# 150308-1-eRIC-Nitro-v1_2.net
KiCad netlist of a schematic drawn in EAGLE
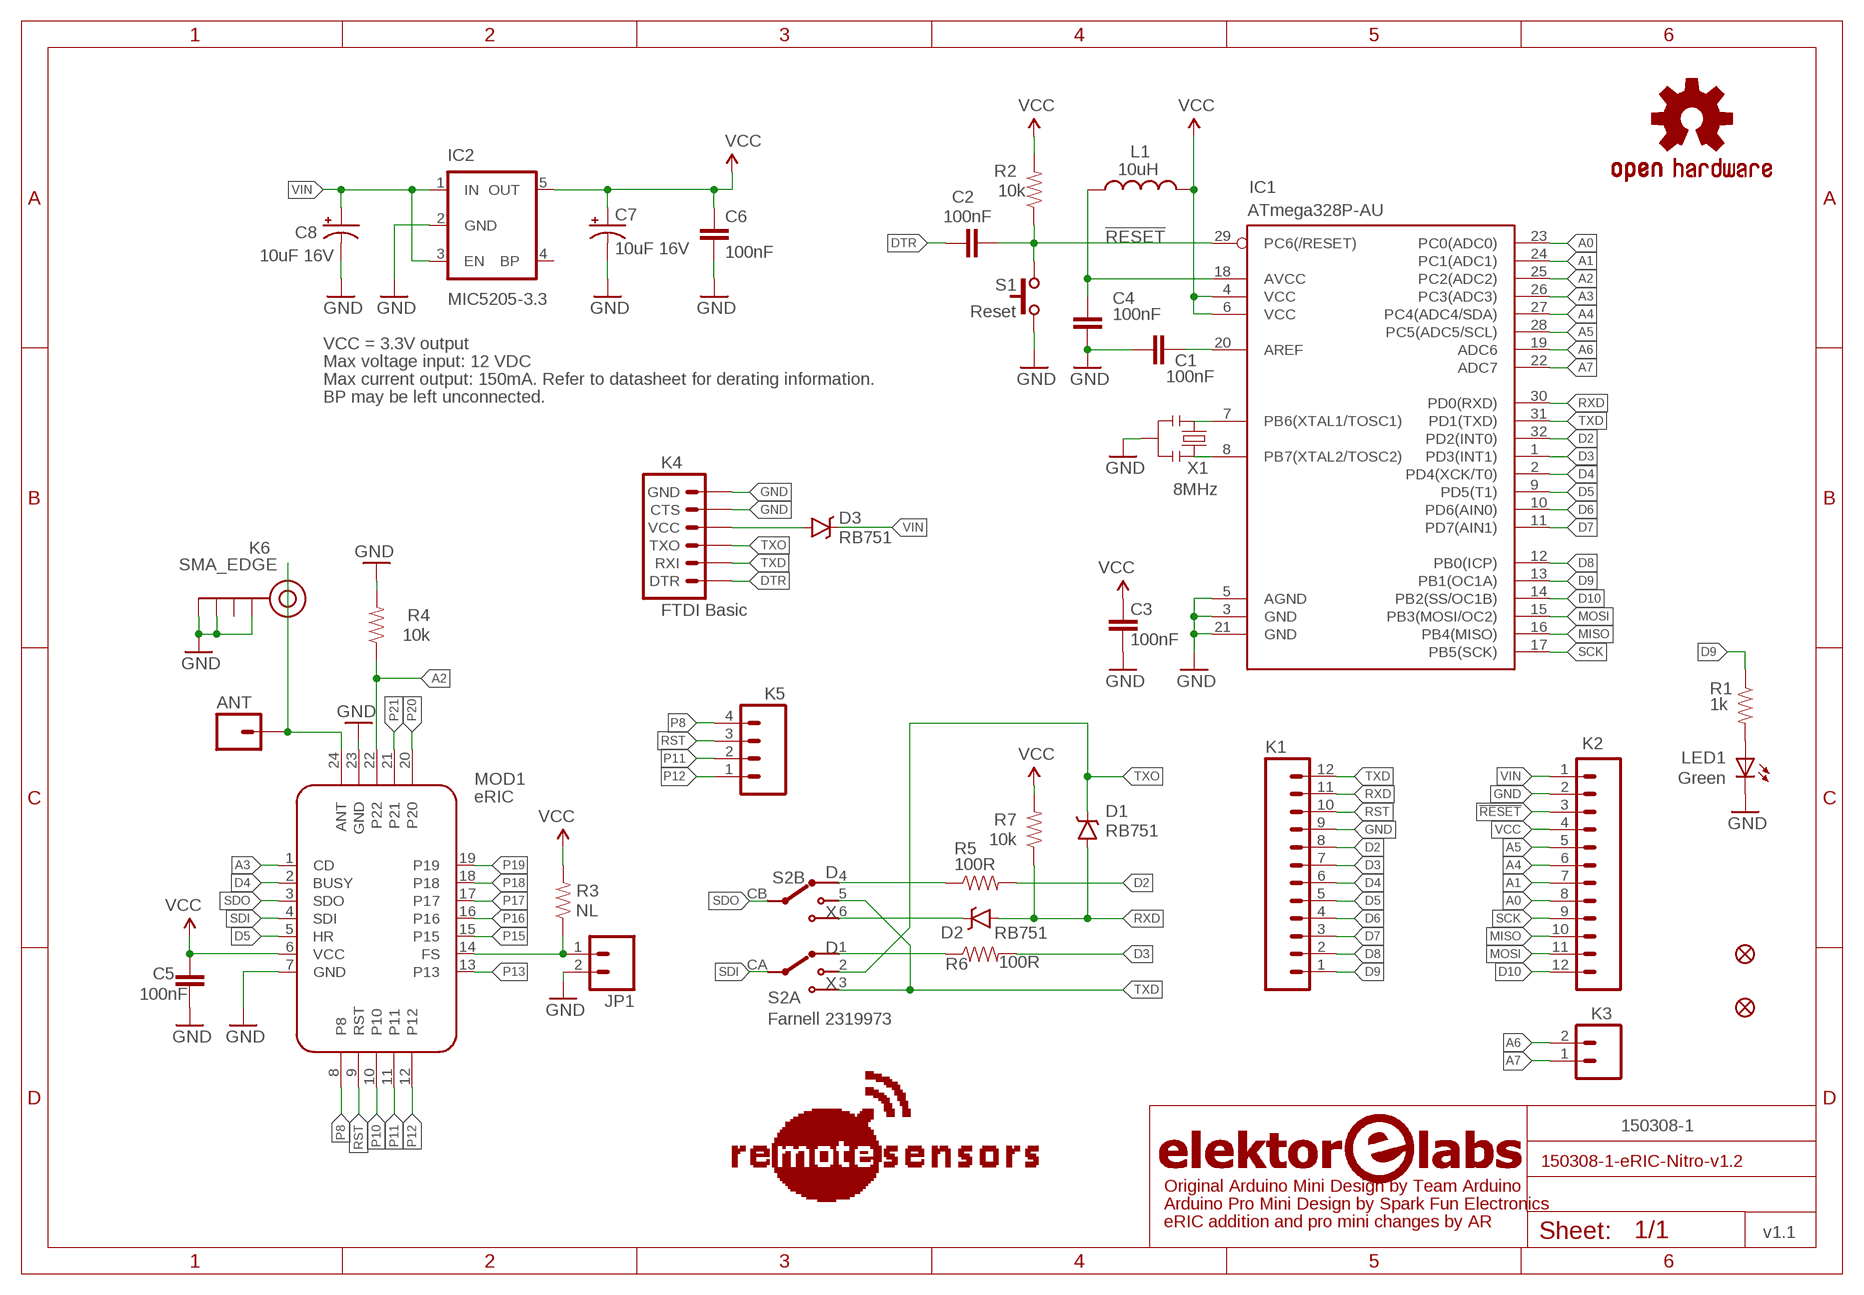
[diagram p0: schematic, sheet 1]

(export (version "E")
  (design (tool "Eeschema 10.0.6"))
  (components
    (comp (ref "ANT")
      (value "M01PTH")
      (footprint "eagle-import:1X01-080")
      (libsource (lib "eagle-import") (part "M01PTH"))
    )
    (comp (ref "C1")
      (value "100nF")
      (footprint "eagle-import:0603-CAP")
      (libsource (lib "eagle-import") (part "CAP0603-CAP"))
    )
    (comp (ref "C2")
      (value "100nF")
      (footprint "eagle-import:0603-CAP")
      (libsource (lib "eagle-import") (part "CAP0603-CAP"))
    )
    (comp (ref "C3")
      (value "100nF")
      (footprint "eagle-import:0603-CAP")
      (libsource (lib "eagle-import") (part "CAP0603-CAP"))
    )
    (comp (ref "C4")
      (value "100nF")
      (footprint "eagle-import:0603-CAP")
      (libsource (lib "eagle-import") (part "CAP0603-CAP"))
    )
    (comp (ref "C5")
      (value "100nF")
      (footprint "eagle-import:0603-CAP")
      (libsource (lib "eagle-import") (part "CAP0603-CAP"))
    )
    (comp (ref "C6")
      (value "100nF")
      (footprint "eagle-import:0603-CAP")
      (libsource (lib "eagle-import") (part "CAP0603-CAP"))
    )
    (comp (ref "C7")
      (value "10uF 16V")
      (footprint "eagle-import:EIA3216")
      (libsource (lib "eagle-import") (part "CAP_POL1206"))
    )
    (comp (ref "C8")
      (value "10uF 16V")
      (footprint "eagle-import:EIA3216")
      (libsource (lib "eagle-import") (part "CAP_POL1206"))
    )
    (comp (ref "D1")
      (value "RB751")
      (footprint "eagle-import:SOD-523")
      (libsource (lib "eagle-import") (part "RB751"))
    )
    (comp (ref "D2")
      (value "RB751")
      (footprint "eagle-import:SOD-523")
      (libsource (lib "eagle-import") (part "RB751"))
    )
    (comp (ref "D3")
      (value "RB751")
      (footprint "eagle-import:SOD-523")
      (libsource (lib "eagle-import") (part "RB751"))
    )
    (comp (ref "FID1")
      (value "FIDUCIALUFIDUCIAL")
      (footprint "eagle-import:MICRO-FIDUCIAL")
      (libsource (lib "eagle-import") (part "FIDUCIALUFIDUCIAL"))
    )
    (comp (ref "FID2")
      (value "FIDUCIALUFIDUCIAL")
      (footprint "eagle-import:MICRO-FIDUCIAL")
      (libsource (lib "eagle-import") (part "FIDUCIALUFIDUCIAL"))
    )
    (comp (ref "IC1")
      (value "ATmega328P-AU")
      (footprint "eagle-import:TQFP32-08")
      (libsource (lib "eagle-import") (part "ATMEGA168"))
    )
    (comp (ref "IC2")
      (value "MIC5205-3.3")
      (footprint "eagle-import:SOT23-5")
      (libsource (lib "eagle-import") (part "V_REG_LDOSMD"))
    )
    (comp (ref "JP1")
      (value "M02PTH")
      (footprint "eagle-import:1X02")
      (libsource (lib "eagle-import") (part "M02PTH"))
    )
    (comp (ref "K1")
      (value "M12PTH")
      (footprint "eagle-import:1X12")
      (libsource (lib "eagle-import") (part "M12PTH"))
    )
    (comp (ref "K2")
      (value "M12PTH")
      (footprint "eagle-import:1X12")
      (libsource (lib "eagle-import") (part "M12PTH"))
    )
    (comp (ref "K3")
      (value "M02PTH")
      (footprint "eagle-import:1X02")
      (libsource (lib "eagle-import") (part "M02PTH"))
    )
    (comp (ref "K4")
      (value "FTDI Basic")
      (footprint "eagle-import:1X06")
      (libsource (lib "eagle-import") (part "ARDUINO_SERIAL_PROGRAMPTH"))
    )
    (comp (ref "K5")
      (value "M04PTH")
      (footprint "eagle-import:1X04")
      (libsource (lib "eagle-import") (part "M04PTH"))
    )
    (comp (ref "K6")
      (value "SMA_EDGE")
      (footprint "eagle-import:SMA-EDGE")
      (libsource (lib "eagle-import") (part "SMA_EDGE"))
    )
    (comp (ref "L1")
      (value "10uH")
      (footprint "eagle-import:0603")
      (libsource (lib "eagle-import") (part "INDUCTOR0603"))
    )
    (comp (ref "LED1")
      (value "Green")
      (footprint "eagle-import:0603-LED-ALT1")
      (libsource (lib "eagle-import") (part "LED"))
    )
    (comp (ref "LOGO1")
      (value "OSHW-LOGOS")
      (footprint "eagle-import:OSHW-LOGO-S")
      (libsource (lib "eagle-import") (part "OSHW-LOGOS"))
    )
    (comp (ref "LOGO2")
      (value "LOGO-ELEKTOR-LABS-25MM")
      (footprint "eagle-import:ELPP-LOGO-ELEKTOR-LABS-25MM")
      (libsource (lib "eagle-import") (part "LOGO-ELEKTOR-LABS-25MM"))
    )
    (comp (ref "LOGO3")
      (value "LOGO-REMOTE-SENSORS-17MM")
      (footprint "eagle-import:LOGO-REMOTE-SENSORS2")
      (libsource (lib "eagle-import") (part "LOGO-REMOTE-SENSORS-17MM"))
    )
    (comp (ref "MOD1")
      (value "eRIC")
      (footprint "eagle-import:ERIC")
      (libsource (lib "eagle-import") (part "ERIC"))
    )
    (comp (ref "R1")
      (value "1k")
      (footprint "eagle-import:0603-RES")
      (libsource (lib "eagle-import") (part "RESISTOR0603-RES"))
    )
    (comp (ref "R2")
      (value "10k")
      (footprint "eagle-import:0603-RES")
      (libsource (lib "eagle-import") (part "RESISTOR0603-RES"))
    )
    (comp (ref "R3")
      (value "NL")
      (footprint "eagle-import:0603-RES")
      (libsource (lib "eagle-import") (part "RESISTOR0603-RES"))
    )
    (comp (ref "R4")
      (value "10k")
      (footprint "eagle-import:0603-RES")
      (libsource (lib "eagle-import") (part "RESISTOR0603-RES"))
    )
    (comp (ref "R5")
      (value "100R")
      (footprint "eagle-import:0603-RES")
      (libsource (lib "eagle-import") (part "SparkFun-Resistors_RESISTOR0603-RES"))
    )
    (comp (ref "R6")
      (value "100R")
      (footprint "eagle-import:0603-RES")
      (libsource (lib "eagle-import") (part "SparkFun-Resistors_RESISTOR0603-RES"))
    )
    (comp (ref "R7")
      (value "10k")
      (footprint "eagle-import:0603-RES")
      (libsource (lib "eagle-import") (part "RESISTOR0603-RES"))
    )
    (comp (ref "S1")
      (value "Reset")
      (footprint "eagle-import:TACTILE-SWITCH-SMD-ALT04")
      (libsource (lib "eagle-import") (part "SWITCH-MOMENTARY-2SMD-ALT04"))
    )
    (comp (ref "S2")
      (value "AYZ0203AGRLC")
      (footprint "eagle-import:AYZ0203")
      (libsource (lib "eagle-import") (part "AYZ0203AGRLC"))
    )
    (comp (ref "X1")
      (value "8MHz")
      (footprint "eagle-import:RESONATOR-SMD")
      (libsource (lib "eagle-import") (part "RESONATORSMD"))
    )
  )
  (nets
    (net (code "1") (name "/~{RESET}") (class "Default")
      (node (ref "C2") (pin "1") (pinfunction "1_1") (pintype "passive"))
      (node (ref "IC1") (pin "29") (pinfunction "PC6(/RESET)_29") (pintype "bidirectional"))
      (node (ref "K2") (pin "3") (pinfunction "3_3") (pintype "passive"))
      (node (ref "R2") (pin "1") (pinfunction "1_1") (pintype "passive"))
      (node (ref "S1") (pin "3") (pinfunction "2_3") (pintype "passive"))
      (node (ref "S1") (pin "4") (pinfunction "2_4") (pintype "passive"))
    )
    (net (code "2") (name "A0") (class "Default")
      (node (ref "IC1") (pin "23") (pinfunction "PC0(ADC0)_23") (pintype "bidirectional"))
      (node (ref "K2") (pin "8") (pinfunction "8_8") (pintype "passive"))
    )
    (net (code "3") (name "A1") (class "Default")
      (node (ref "IC1") (pin "24") (pinfunction "PC1(ADC1)_24") (pintype "bidirectional"))
      (node (ref "K2") (pin "7") (pinfunction "7_7") (pintype "passive"))
    )
    (net (code "4") (name "A2") (class "Default")
      (node (ref "IC1") (pin "25") (pinfunction "PC2(ADC2)_25") (pintype "bidirectional"))
      (node (ref "MOD1") (pin "22") (pinfunction "P22_22") (pintype "bidirectional"))
      (node (ref "R4") (pin "1") (pinfunction "1_1") (pintype "passive"))
    )
    (net (code "5") (name "A3") (class "Default")
      (node (ref "IC1") (pin "26") (pinfunction "PC3(ADC3)_26") (pintype "bidirectional"))
      (node (ref "MOD1") (pin "1") (pinfunction "CD_1") (pintype "bidirectional"))
    )
    (net (code "6") (name "A4") (class "Default")
      (node (ref "IC1") (pin "27") (pinfunction "PC4(ADC4/SDA)_27") (pintype "bidirectional"))
      (node (ref "K2") (pin "6") (pinfunction "6_6") (pintype "passive"))
    )
    (net (code "7") (name "A5") (class "Default")
      (node (ref "IC1") (pin "28") (pinfunction "PC5(ADC5/SCL)_28") (pintype "bidirectional"))
      (node (ref "K2") (pin "5") (pinfunction "5_5") (pintype "passive"))
    )
    (net (code "8") (name "A6") (class "Default")
      (node (ref "IC1") (pin "19") (pinfunction "ADC6_19") (pintype "bidirectional"))
      (node (ref "K3") (pin "2") (pinfunction "2_2") (pintype "passive"))
    )
    (net (code "9") (name "A7") (class "Default")
      (node (ref "IC1") (pin "22") (pinfunction "ADC7_22") (pintype "bidirectional"))
      (node (ref "K3") (pin "1") (pinfunction "1_1") (pintype "passive"))
    )
    (net (code "10") (name "D2") (class "Default")
      (node (ref "IC1") (pin "32") (pinfunction "PD2(INT0)_32") (pintype "bidirectional"))
      (node (ref "K1") (pin "8") (pinfunction "8_8") (pintype "passive"))
      (node (ref "R5") (pin "2") (pinfunction "2_2") (pintype "passive"))
    )
    (net (code "11") (name "D3") (class "Default")
      (node (ref "IC1") (pin "1") (pinfunction "PD3(INT1)_1") (pintype "bidirectional"))
      (node (ref "K1") (pin "7") (pinfunction "7_7") (pintype "passive"))
      (node (ref "R6") (pin "2") (pinfunction "2_2") (pintype "passive"))
    )
    (net (code "12") (name "D4") (class "Default")
      (node (ref "IC1") (pin "2") (pinfunction "PD4(XCK/T0)_2") (pintype "bidirectional"))
      (node (ref "K1") (pin "6") (pinfunction "6_6") (pintype "passive"))
      (node (ref "MOD1") (pin "2") (pinfunction "BUSY_2") (pintype "bidirectional"))
    )
    (net (code "13") (name "D5") (class "Default")
      (node (ref "IC1") (pin "9") (pinfunction "PD5(T1)_9") (pintype "bidirectional"))
      (node (ref "K1") (pin "5") (pinfunction "5_5") (pintype "passive"))
      (node (ref "MOD1") (pin "5") (pinfunction "HR_5") (pintype "bidirectional"))
    )
    (net (code "14") (name "D6") (class "Default")
      (node (ref "IC1") (pin "10") (pinfunction "PD6(AIN0)_10") (pintype "bidirectional"))
      (node (ref "K1") (pin "4") (pinfunction "4_4") (pintype "passive"))
    )
    (net (code "15") (name "D7") (class "Default")
      (node (ref "IC1") (pin "11") (pinfunction "PD7(AIN1)_11") (pintype "bidirectional"))
      (node (ref "K1") (pin "3") (pinfunction "3_3") (pintype "passive"))
    )
    (net (code "16") (name "D8") (class "Default")
      (node (ref "IC1") (pin "12") (pinfunction "PB0(ICP)_12") (pintype "bidirectional"))
      (node (ref "K1") (pin "2") (pinfunction "2_2") (pintype "passive"))
    )
    (net (code "17") (name "D9") (class "Default")
      (node (ref "IC1") (pin "13") (pinfunction "PB1(OC1A)_13") (pintype "bidirectional"))
      (node (ref "K1") (pin "1") (pinfunction "1_1") (pintype "passive"))
      (node (ref "R1") (pin "1") (pinfunction "1_1") (pintype "passive"))
    )
    (net (code "18") (name "D10") (class "Default")
      (node (ref "IC1") (pin "14") (pinfunction "PB2(SS/OC1B)_14") (pintype "bidirectional"))
      (node (ref "K2") (pin "12") (pinfunction "12_12") (pintype "passive"))
    )
    (net (code "19") (name "DTR") (class "Default")
      (node (ref "C2") (pin "2") (pinfunction "2_2") (pintype "passive"))
      (node (ref "K4") (pin "1") (pinfunction "DTR_1") (pintype "passive"))
    )
    (net (code "20") (name "GND") (class "Default")
      (node (ref "C1") (pin "1") (pinfunction "1_1") (pintype "passive"))
      (node (ref "C3") (pin "1") (pinfunction "1_1") (pintype "passive"))
      (node (ref "C4") (pin "1") (pinfunction "1_1") (pintype "passive"))
      (node (ref "C5") (pin "1") (pinfunction "1_1") (pintype "passive"))
      (node (ref "C6") (pin "2") (pinfunction "2_2") (pintype "passive"))
      (node (ref "C7") (pin "C") (pinfunction "-_C") (pintype "passive"))
      (node (ref "C8") (pin "C") (pinfunction "-_C") (pintype "passive"))
      (node (ref "IC1") (pin "21") (pinfunction "GND_21") (pintype "bidirectional"))
      (node (ref "IC1") (pin "3") (pinfunction "GND_3") (pintype "bidirectional"))
      (node (ref "IC1") (pin "5") (pinfunction "AGND_5") (pintype "bidirectional"))
      (node (ref "IC2") (pin "2") (pinfunction "GND_2") (pintype "input"))
      (node (ref "JP1") (pin "2") (pinfunction "2_2") (pintype "passive"))
      (node (ref "K1") (pin "9") (pinfunction "9_9") (pintype "passive"))
      (node (ref "K2") (pin "2") (pinfunction "2_2") (pintype "passive"))
      (node (ref "K4") (pin "5") (pinfunction "CTS_5") (pintype "passive"))
      (node (ref "K4") (pin "6") (pinfunction "GND_6") (pintype "passive"))
      (node (ref "K6") (pin "GND@0") (pinfunction "GND_GND@0") (pintype "bidirectional"))
      (node (ref "K6") (pin "GND@2") (pinfunction "GND_GND@2") (pintype "bidirectional"))
      (node (ref "K6") (pin "GND@3") (pinfunction "GND_GND@3") (pintype "bidirectional"))
      (node (ref "LED1") (pin "C") (pinfunction "C_C") (pintype "passive"))
      (node (ref "MOD1") (pin "23") (pinfunction "GND_23") (pintype "bidirectional"))
      (node (ref "MOD1") (pin "7") (pinfunction "GND_7") (pintype "power_in"))
      (node (ref "R4") (pin "2") (pinfunction "2_2") (pintype "passive"))
      (node (ref "S1") (pin "1") (pinfunction "1_1") (pintype "passive"))
      (node (ref "S1") (pin "2") (pinfunction "1_2") (pintype "passive"))
      (node (ref "X1") (pin "2") (pinfunction "2_2") (pintype "passive"))
    )
    (net (code "21") (name "MISO") (class "Default")
      (node (ref "IC1") (pin "16") (pinfunction "PB4(MISO)_16") (pintype "bidirectional"))
      (node (ref "K2") (pin "10") (pinfunction "10_10") (pintype "passive"))
    )
    (net (code "22") (name "MOSI") (class "Default")
      (node (ref "IC1") (pin "15") (pinfunction "PB3(MOSI/OC2)_15") (pintype "bidirectional"))
      (node (ref "K2") (pin "11") (pinfunction "11_11") (pintype "passive"))
    )
    (net (code "23") (name "Net-(IC1-AREF)") (class "Default")
      (node (ref "C1") (pin "2") (pinfunction "2_2") (pintype "passive"))
      (node (ref "IC1") (pin "20") (pinfunction "AREF_20") (pintype "bidirectional"))
    )
    (net (code "24") (name "Net-(IC1-AVCC)") (class "Default")
      (node (ref "C4") (pin "2") (pinfunction "2_2") (pintype "passive"))
      (node (ref "IC1") (pin "18") (pinfunction "AVCC_18") (pintype "bidirectional"))
      (node (ref "L1") (pin "1") (pinfunction "1_1") (pintype "passive"))
    )
    (net (code "25") (name "Net-(IC1-PB6(XTAL1{slash}TOSC1))") (class "Default")
      (node (ref "IC1") (pin "7") (pinfunction "PB6(XTAL1/TOSC1)_7") (pintype "bidirectional"))
      (node (ref "X1") (pin "1") (pinfunction "1_1") (pintype "passive"))
    )
    (net (code "26") (name "Net-(IC1-PB7(XTAL2{slash}TOSC2))") (class "Default")
      (node (ref "IC1") (pin "8") (pinfunction "PB7(XTAL2/TOSC2)_8") (pintype "bidirectional"))
      (node (ref "X1") (pin "3") (pinfunction "3_3") (pintype "passive"))
    )
    (net (code "27") (name "Net-(K4-VCC)") (class "Default")
      (node (ref "D3") (pin "A") (pinfunction "A_A") (pintype "passive"))
      (node (ref "K4") (pin "4") (pinfunction "VCC_4") (pintype "passive"))
    )
    (net (code "28") (name "Net-(K6-SIGNAL)") (class "Default")
      (node (ref "ANT") (pin "1") (pinfunction "1_1") (pintype "passive"))
      (node (ref "K6") (pin "SIG") (pinfunction "SIGNAL_SIG") (pintype "bidirectional"))
      (node (ref "MOD1") (pin "24") (pinfunction "ANT_24") (pintype "bidirectional"))
    )
    (net (code "29") (name "Net-(LED1-PadA)") (class "Default")
      (node (ref "LED1") (pin "A") (pinfunction "A_A") (pintype "passive"))
      (node (ref "R1") (pin "2") (pinfunction "2_2") (pintype "passive"))
    )
    (net (code "30") (name "Net-(MOD1-FS)") (class "Default")
      (node (ref "JP1") (pin "1") (pinfunction "1_1") (pintype "passive"))
      (node (ref "MOD1") (pin "14") (pinfunction "FS_14") (pintype "bidirectional"))
      (node (ref "R3") (pin "1") (pinfunction "1_1") (pintype "passive"))
    )
    (net (code "31") (name "Net-(R6-Pad1)") (class "Default")
      (node (ref "R6") (pin "1") (pinfunction "1_1") (pintype "passive"))
      (node (ref "S2") (pin "1") (pinfunction "1_1") (pintype "bidirectional"))
    )
    (net (code "32") (name "Net-(S2B-1)") (class "Default")
      (node (ref "R5") (pin "1") (pinfunction "1_1") (pintype "passive"))
      (node (ref "S2") (pin "4") (pinfunction "1_4") (pintype "bidirectional"))
    )
    (net (code "33") (name "Net-(S2B-3)") (class "Default")
      (node (ref "D2") (pin "C") (pinfunction "C_C") (pintype "passive"))
      (node (ref "S2") (pin "6") (pinfunction "3_6") (pintype "bidirectional"))
    )
    (net (code "34") (name "P8") (class "Default")
      (node (ref "K5") (pin "4") (pinfunction "4_4") (pintype "passive"))
      (node (ref "MOD1") (pin "8") (pinfunction "P8_8") (pintype "bidirectional"))
    )
    (net (code "35") (name "P10") (class "Default")
      (node (ref "MOD1") (pin "10") (pinfunction "P10_10") (pintype "bidirectional"))
    )
    (net (code "36") (name "P11") (class "Default")
      (node (ref "K5") (pin "2") (pinfunction "2_2") (pintype "passive"))
      (node (ref "MOD1") (pin "11") (pinfunction "P11_11") (pintype "bidirectional"))
    )
    (net (code "37") (name "P12") (class "Default")
      (node (ref "K5") (pin "1") (pinfunction "1_1") (pintype "passive"))
      (node (ref "MOD1") (pin "12") (pinfunction "P12_12") (pintype "bidirectional"))
    )
    (net (code "38") (name "P13") (class "Default")
      (node (ref "MOD1") (pin "13") (pinfunction "P13_13") (pintype "bidirectional"))
    )
    (net (code "39") (name "P15") (class "Default")
      (node (ref "MOD1") (pin "15") (pinfunction "P15_15") (pintype "bidirectional"))
    )
    (net (code "40") (name "P16") (class "Default")
      (node (ref "MOD1") (pin "16") (pinfunction "P16_16") (pintype "bidirectional"))
    )
    (net (code "41") (name "P17") (class "Default")
      (node (ref "MOD1") (pin "17") (pinfunction "P17_17") (pintype "bidirectional"))
    )
    (net (code "42") (name "P18") (class "Default")
      (node (ref "MOD1") (pin "18") (pinfunction "P18_18") (pintype "bidirectional"))
    )
    (net (code "43") (name "P19") (class "Default")
      (node (ref "MOD1") (pin "19") (pinfunction "P19_19") (pintype "bidirectional"))
    )
    (net (code "44") (name "P20") (class "Default")
      (node (ref "MOD1") (pin "20") (pinfunction "P20_20") (pintype "bidirectional"))
    )
    (net (code "45") (name "P21") (class "Default")
      (node (ref "MOD1") (pin "21") (pinfunction "P21_21") (pintype "bidirectional"))
    )
    (net (code "46") (name "RST") (class "Default")
      (node (ref "K1") (pin "10") (pinfunction "10_10") (pintype "passive"))
      (node (ref "K5") (pin "3") (pinfunction "3_3") (pintype "passive"))
      (node (ref "MOD1") (pin "9") (pinfunction "RST_9") (pintype "bidirectional"))
    )
    (net (code "47") (name "RXD") (class "Default")
      (node (ref "D1") (pin "A") (pinfunction "A_A") (pintype "passive"))
      (node (ref "D2") (pin "A") (pinfunction "A_A") (pintype "passive"))
      (node (ref "IC1") (pin "30") (pinfunction "PD0(RXD)_30") (pintype "bidirectional"))
      (node (ref "K1") (pin "11") (pinfunction "11_11") (pintype "passive"))
      (node (ref "R7") (pin "1") (pinfunction "1_1") (pintype "passive"))
    )
    (net (code "48") (name "SCK") (class "Default")
      (node (ref "IC1") (pin "17") (pinfunction "PB5(SCK)_17") (pintype "bidirectional"))
      (node (ref "K2") (pin "9") (pinfunction "9_9") (pintype "passive"))
    )
    (net (code "49") (name "SDI") (class "Default")
      (node (ref "MOD1") (pin "4") (pinfunction "SDI_4") (pintype "bidirectional"))
      (node (ref "S2") (pin "CA") (pinfunction "2_CA") (pintype "bidirectional"))
    )
    (net (code "50") (name "SDO") (class "Default")
      (node (ref "MOD1") (pin "3") (pinfunction "SDO_3") (pintype "bidirectional"))
      (node (ref "S2") (pin "CB") (pinfunction "2_CB") (pintype "bidirectional"))
    )
    (net (code "51") (name "TXD") (class "Default")
      (node (ref "IC1") (pin "31") (pinfunction "PD1(TXD)_31") (pintype "bidirectional"))
      (node (ref "K1") (pin "12") (pinfunction "12_12") (pintype "passive"))
      (node (ref "K4") (pin "2") (pinfunction "RXI_2") (pintype "passive"))
      (node (ref "S2") (pin "3") (pinfunction "3_3") (pintype "bidirectional"))
      (node (ref "S2") (pin "5") (pinfunction "7_5") (pintype "bidirectional"))
    )
    (net (code "52") (name "TXO") (class "Default")
      (node (ref "D1") (pin "C") (pinfunction "C_C") (pintype "passive"))
      (node (ref "K4") (pin "3") (pinfunction "TXO_3") (pintype "passive"))
      (node (ref "S2") (pin "2") (pinfunction "7_2") (pintype "bidirectional"))
    )
    (net (code "53") (name "VCC") (class "Default")
      (node (ref "C3") (pin "2") (pinfunction "2_2") (pintype "passive"))
      (node (ref "C5") (pin "2") (pinfunction "2_2") (pintype "passive"))
      (node (ref "C6") (pin "1") (pinfunction "1_1") (pintype "passive"))
      (node (ref "C7") (pin "A") (pinfunction "+_A") (pintype "passive"))
      (node (ref "IC1") (pin "4") (pinfunction "VCC_4") (pintype "bidirectional"))
      (node (ref "IC1") (pin "6") (pinfunction "VCC_6") (pintype "bidirectional"))
      (node (ref "IC2") (pin "5") (pinfunction "OUT_5") (pintype "passive"))
      (node (ref "K2") (pin "4") (pinfunction "4_4") (pintype "passive"))
      (node (ref "L1") (pin "2") (pinfunction "2_2") (pintype "passive"))
      (node (ref "MOD1") (pin "6") (pinfunction "VCC_6") (pintype "power_in"))
      (node (ref "R2") (pin "2") (pinfunction "2_2") (pintype "passive"))
      (node (ref "R3") (pin "2") (pinfunction "2_2") (pintype "passive"))
      (node (ref "R7") (pin "2") (pinfunction "2_2") (pintype "passive"))
    )
    (net (code "54") (name "VIN") (class "Default")
      (node (ref "C8") (pin "A") (pinfunction "+_A") (pintype "passive"))
      (node (ref "D3") (pin "C") (pinfunction "C_C") (pintype "passive"))
      (node (ref "IC2") (pin "1") (pinfunction "IN_1") (pintype "input"))
      (node (ref "IC2") (pin "3") (pinfunction "EN_3") (pintype "input"))
      (node (ref "K2") (pin "1") (pinfunction "1_1") (pintype "passive"))
    )
    (net (code "55") (name "unconnected-(IC2-BP-Pad4)") (class "Default")
      (node (ref "IC2") (pin "4") (pinfunction "BP_4") (pintype "input"))
    )
    (net (code "56") (name "unconnected-(K6-GND-PadGND@1)") (class "Default")
      (node (ref "K6") (pin "GND@1") (pinfunction "GND_GND@1") (pintype "bidirectional"))
    )
  )
)
